# PowerSupply-5V-3_3V-v10.net
KiCad netlist of a schematic drawn in EAGLE
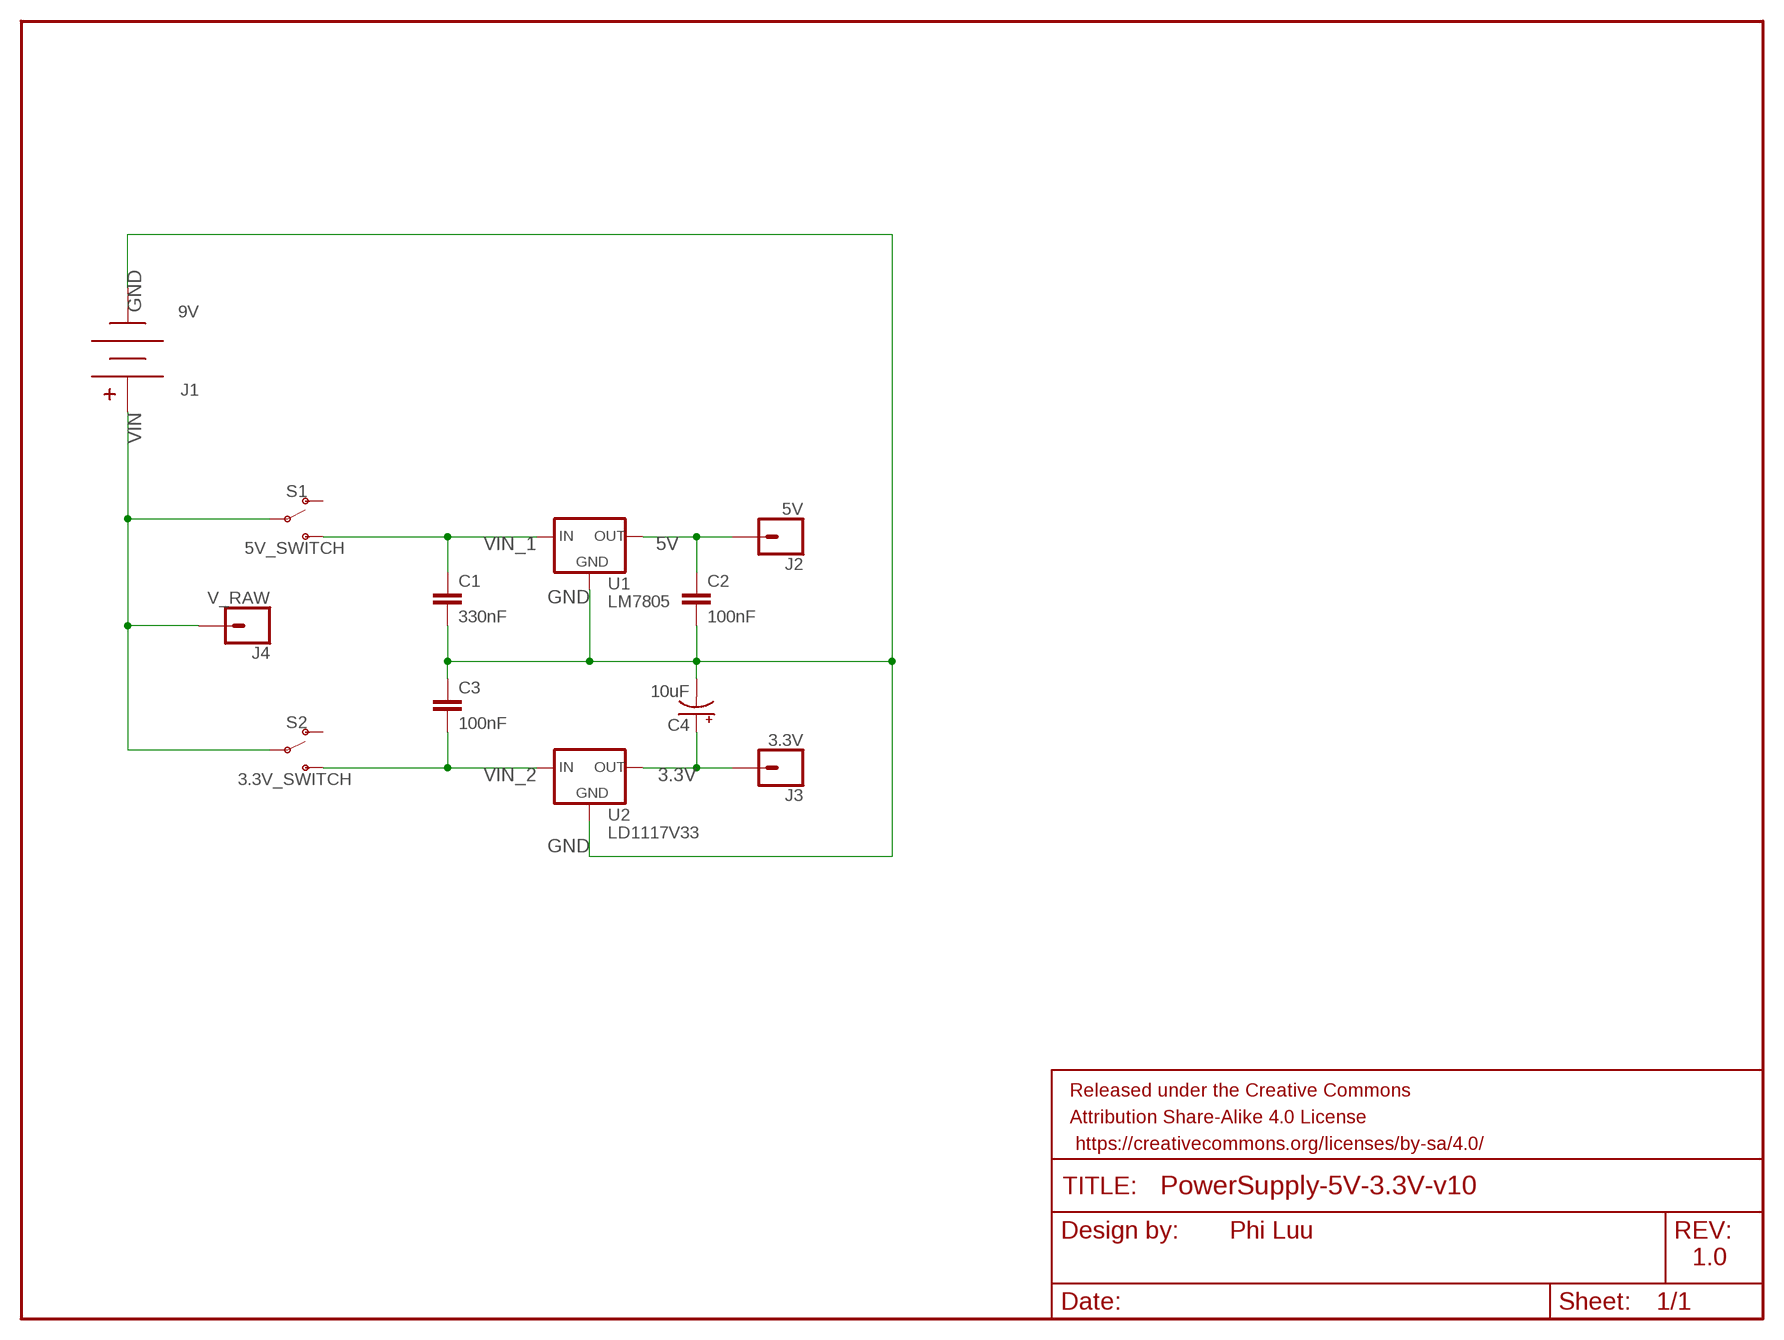
[diagram p0: schematic, sheet 1]

(export (version "E")
  (design (tool "Eeschema 10.0.6"))
  (components
    (comp (ref "C1")
      (value "330nF")
      (footprint "eagle-import:CAP-PTH-SMALL-KIT")
      (libsource (lib "eagle-import") (part "0.1UF-KIT-EZ-50V-20%"))
    )
    (comp (ref "C2")
      (value "100nF")
      (footprint "eagle-import:CAP-PTH-SMALL-KIT")
      (libsource (lib "eagle-import") (part "0.1UF-KIT-EZ-50V-20%"))
    )
    (comp (ref "C3")
      (value "100nF")
      (footprint "eagle-import:CAP-PTH-SMALL-KIT")
      (libsource (lib "eagle-import") (part "0.1UF-KIT-EZ-50V-20%"))
    )
    (comp (ref "C4")
      (value "10uF")
      (footprint "eagle-import:CPOL-RADIAL-2.5MM-5MM")
      (libsource (lib "eagle-import") (part "10UF-POLAR-RADIAL-2.5MM-25V-20%"))
    )
    (comp (ref "FRAME1")
      (value "FRAME-LETTER")
      (footprint "eagle-import:CREATIVE_COMMONS")
      (libsource (lib "eagle-import") (part "FRAME-LETTER"))
    )
    (comp (ref "J1")
      (value "9V")
      (footprint "eagle-import:BC9VPC")
      (libsource (lib "eagle-import") (part "BC9VPC"))
    )
    (comp (ref "J2")
      (value "5V")
      (footprint "eagle-import:1X01")
      (libsource (lib "eagle-import") (part "CONN_01"))
    )
    (comp (ref "J3")
      (value "3.3V")
      (footprint "eagle-import:1X01")
      (libsource (lib "eagle-import") (part "CONN_01"))
    )
    (comp (ref "J4")
      (value "V_RAW")
      (footprint "eagle-import:1X01")
      (libsource (lib "eagle-import") (part "CONN_01"))
    )
    (comp (ref "S1")
      (value "5V_SWITCH")
      (footprint "eagle-import:SWITCH_SPDT_PTH_11.6X4.0MM")
      (libsource (lib "eagle-import") (part "SWITCH-SPDT-PTH-11.6X4.0MM"))
    )
    (comp (ref "S2")
      (value "3.3V_SWITCH")
      (footprint "eagle-import:SWITCH_SPDT_PTH_11.6X4.0MM")
      (libsource (lib "eagle-import") (part "SWITCH-SPDT-PTH-11.6X4.0MM"))
    )
    (comp (ref "U1")
      (value "LM7805")
      (footprint "eagle-import:TO-220-ALT")
      (libsource (lib "eagle-import") (part "V_REG_78XX-TO-220"))
    )
    (comp (ref "U2")
      (value "LD1117V33")
      (footprint "eagle-import:78XXL")
      (libsource (lib "eagle-import") (part "V_REG_LD1117VXX"))
    )
  )
  (nets
    (net (code "1") (name "/3.3V") (class "Default")
      (node (ref "C4") (pin "1") (pinfunction "+_1") (pintype "passive"))
      (node (ref "J3") (pin "1") (pinfunction "1_1") (pintype "passive"))
      (node (ref "U2") (pin "GND") (pinfunction "OUT_GND") (pintype "passive"))
    )
    (net (code "2") (name "/5V") (class "Default")
      (node (ref "C2") (pin "1") (pinfunction "1_1") (pintype "passive"))
      (node (ref "J2") (pin "1") (pinfunction "1_1") (pintype "passive"))
      (node (ref "U1") (pin "OUT") (pinfunction "OUT_OUT") (pintype "passive"))
    )
    (net (code "3") (name "/GND") (class "Default")
      (node (ref "C1") (pin "2") (pinfunction "2_2") (pintype "passive"))
      (node (ref "C2") (pin "2") (pinfunction "2_2") (pintype "passive"))
      (node (ref "C3") (pin "1") (pinfunction "1_1") (pintype "passive"))
      (node (ref "C4") (pin "2") (pinfunction "-_2") (pintype "passive"))
      (node (ref "J1") (pin "V-") (pinfunction "V-_V-") (pintype "bidirectional"))
      (node (ref "U1") (pin "GND") (pinfunction "GND_GND") (pintype "input"))
      (node (ref "U2") (pin "IN") (pinfunction "GND_IN") (pintype "input"))
    )
    (net (code "4") (name "/VIN") (class "Default")
      (node (ref "J1") (pin "V+") (pinfunction "V+_V+") (pintype "bidirectional"))
      (node (ref "J4") (pin "1") (pinfunction "1_1") (pintype "passive"))
      (node (ref "S1") (pin "2") (pinfunction "P_2") (pintype "passive"))
      (node (ref "S2") (pin "2") (pinfunction "P_2") (pintype "passive"))
    )
    (net (code "5") (name "/VIN_1") (class "Default")
      (node (ref "C1") (pin "1") (pinfunction "1_1") (pintype "passive"))
      (node (ref "S1") (pin "3") (pinfunction "S_3") (pintype "passive"))
      (node (ref "U1") (pin "IN") (pinfunction "IN_IN") (pintype "input"))
    )
    (net (code "6") (name "/VIN_2") (class "Default")
      (node (ref "C3") (pin "2") (pinfunction "2_2") (pintype "passive"))
      (node (ref "S2") (pin "3") (pinfunction "S_3") (pintype "passive"))
      (node (ref "U2") (pin "OUT") (pinfunction "IN_OUT") (pintype "input"))
    )
    (net (code "7") (name "unconnected-(S1-O-Pad1)") (class "Default")
      (node (ref "S1") (pin "1") (pinfunction "O_1") (pintype "passive"))
    )
    (net (code "8") (name "unconnected-(S2-O-Pad1)") (class "Default")
      (node (ref "S2") (pin "1") (pinfunction "O_1") (pintype "passive"))
    )
  )
)
